# SMD_cree_driver_led-mosfet001.net
KiCad netlist of a schematic drawn in EAGLE
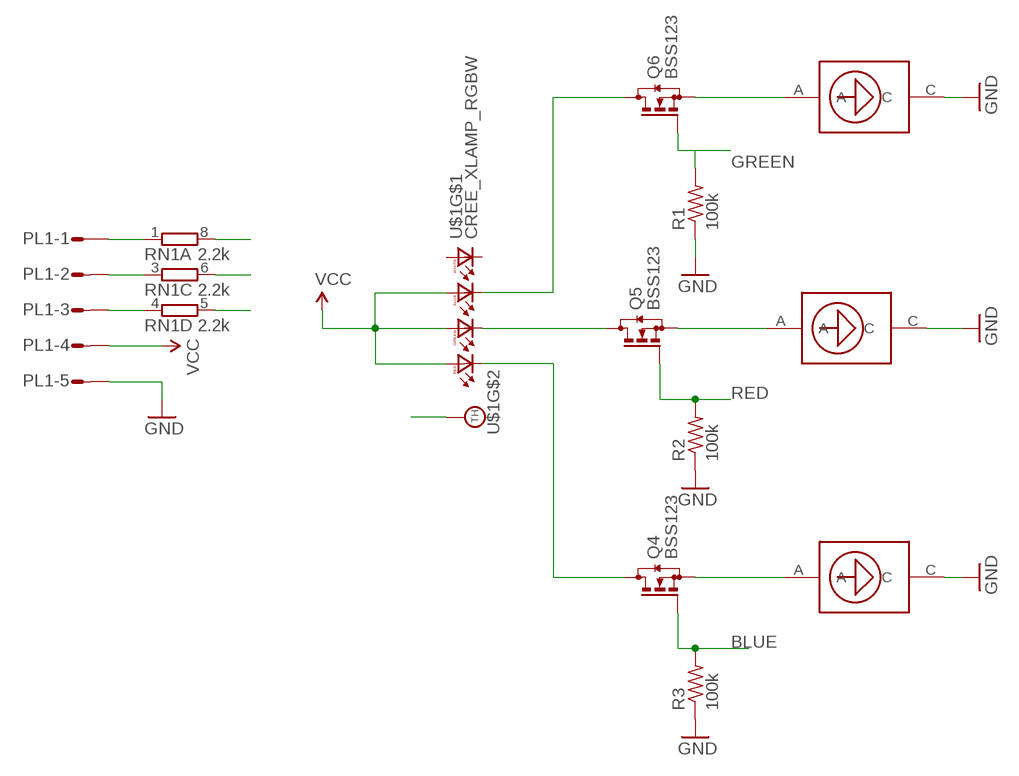
[diagram p0: schematic, sheet 1]

(export (version "E")
  (design (tool "Eeschema 10.0.6"))
  (components
    (comp (ref "PL1")
      (value "DF3-05R")
      (footprint "eagle-import:DF3R-05")
      (libsource (lib "eagle-import") (part "DF3-05R"))
    )
    (comp (ref "Q4")
      (value "BSS123")
      (footprint "eagle-import:SOT23")
      (libsource (lib "eagle-import") (part "BSS123"))
    )
    (comp (ref "Q5")
      (value "BSS123")
      (footprint "eagle-import:SOT23")
      (libsource (lib "eagle-import") (part "BSS123"))
    )
    (comp (ref "Q6")
      (value "BSS123")
      (footprint "eagle-import:SOT23")
      (libsource (lib "eagle-import") (part "BSS123"))
    )
    (comp (ref "R1")
      (value "100k")
      (footprint "eagle-import:R0402")
      (libsource (lib "eagle-import") (part "R-US_R0402"))
    )
    (comp (ref "R2")
      (value "100k")
      (footprint "eagle-import:R0402")
      (libsource (lib "eagle-import") (part "R-US_R0402"))
    )
    (comp (ref "R3")
      (value "100k")
      (footprint "eagle-import:R0402")
      (libsource (lib "eagle-import") (part "R-US_R0402"))
    )
    (comp (ref "RN1")
      (value "2.2k")
      (footprint "eagle-import:0603-ARC")
      (libsource (lib "eagle-import") (part "4R-N0603-ARC"))
    )
    (comp (ref "U$1")
      (value "CREE_XLAMP_RGBW")
      (footprint "eagle-import:CREE_XLAMP_XML")
      (libsource (lib "eagle-import") (part "CREE_XLAMP_RGBW"))
    )
    (comp (ref "U$2")
      (value "NSI50350AST3G")
      (footprint "eagle-import:SMC-2")
      (libsource (lib "eagle-import") (part "NSI50350AST3G"))
    )
    (comp (ref "U$3")
      (value "NSI50350AST3G")
      (footprint "eagle-import:SMC-2")
      (libsource (lib "eagle-import") (part "NSI50350AST3G"))
    )
    (comp (ref "U$4")
      (value "NSI50350AST3G")
      (footprint "eagle-import:SMC-2")
      (libsource (lib "eagle-import") (part "NSI50350AST3G"))
    )
  )
  (nets
    (net (code "1") (name "/BLUE") (class "Default")
      (node (ref "Q4") (pin "1") (pinfunction "G_1") (pintype "passive"))
      (node (ref "R3") (pin "2") (pinfunction "2_2") (pintype "passive"))
      (node (ref "RN1") (pin "5") (pinfunction "2_5") (pintype "passive"))
    )
    (net (code "2") (name "/GREEN") (class "Default")
      (node (ref "Q6") (pin "1") (pinfunction "G_1") (pintype "passive"))
      (node (ref "R1") (pin "2") (pinfunction "2_2") (pintype "passive"))
      (node (ref "RN1") (pin "8") (pinfunction "2_8") (pintype "passive"))
    )
    (net (code "3") (name "/RED") (class "Default")
      (node (ref "Q5") (pin "1") (pinfunction "G_1") (pintype "passive"))
      (node (ref "R2") (pin "2") (pinfunction "2_2") (pintype "passive"))
      (node (ref "RN1") (pin "6") (pinfunction "2_6") (pintype "passive"))
    )
    (net (code "4") (name "GND") (class "Default")
      (node (ref "PL1") (pin "5") (pinfunction "S_5") (pintype "passive"))
      (node (ref "R1") (pin "1") (pinfunction "1_1") (pintype "passive"))
      (node (ref "R2") (pin "1") (pinfunction "1_1") (pintype "passive"))
      (node (ref "R3") (pin "1") (pinfunction "1_1") (pintype "passive"))
      (node (ref "U$2") (pin "C") (pinfunction "C_C") (pintype "bidirectional"))
      (node (ref "U$3") (pin "C") (pinfunction "C_C") (pintype "bidirectional"))
      (node (ref "U$4") (pin "C") (pinfunction "C_C") (pintype "bidirectional"))
    )
    (net (code "5") (name "Net-(PL1A-S)") (class "Default")
      (node (ref "PL1") (pin "1") (pinfunction "S_1") (pintype "passive"))
      (node (ref "RN1") (pin "1") (pinfunction "1_1") (pintype "passive"))
    )
    (net (code "6") (name "Net-(PL1B-S)") (class "Default")
      (node (ref "PL1") (pin "2") (pinfunction "S_2") (pintype "passive"))
      (node (ref "RN1") (pin "3") (pinfunction "1_3") (pintype "passive"))
    )
    (net (code "7") (name "Net-(PL1C-S)") (class "Default")
      (node (ref "PL1") (pin "3") (pinfunction "S_3") (pintype "passive"))
      (node (ref "RN1") (pin "4") (pinfunction "1_4") (pintype "passive"))
    )
    (net (code "8") (name "Net-(Q4-D)") (class "Default")
      (node (ref "Q4") (pin "3") (pinfunction "D_3") (pintype "passive"))
      (node (ref "U$1") (pin "8") (pinfunction "RC_8") (pintype "passive"))
    )
    (net (code "9") (name "Net-(Q4-S)") (class "Default")
      (node (ref "Q4") (pin "2") (pinfunction "S_2") (pintype "passive"))
      (node (ref "U$4") (pin "A") (pinfunction "A_A") (pintype "bidirectional"))
    )
    (net (code "10") (name "Net-(Q5-D)") (class "Default")
      (node (ref "Q5") (pin "3") (pinfunction "D_3") (pintype "passive"))
      (node (ref "U$1") (pin "7") (pinfunction "GC_7") (pintype "passive"))
    )
    (net (code "11") (name "Net-(Q5-S)") (class "Default")
      (node (ref "Q5") (pin "2") (pinfunction "S_2") (pintype "passive"))
      (node (ref "U$3") (pin "A") (pinfunction "A_A") (pintype "bidirectional"))
    )
    (net (code "12") (name "Net-(Q6-D)") (class "Default")
      (node (ref "Q6") (pin "3") (pinfunction "D_3") (pintype "passive"))
      (node (ref "U$1") (pin "6") (pinfunction "BC_6") (pintype "passive"))
    )
    (net (code "13") (name "Net-(Q6-S)") (class "Default")
      (node (ref "Q6") (pin "2") (pinfunction "S_2") (pintype "passive"))
      (node (ref "U$2") (pin "A") (pinfunction "A_A") (pintype "bidirectional"))
    )
    (net (code "14") (name "VCC") (class "Default")
      (node (ref "PL1") (pin "4") (pinfunction "S_4") (pintype "passive"))
      (node (ref "U$1") (pin "1") (pinfunction "RA_1") (pintype "passive"))
      (node (ref "U$1") (pin "2") (pinfunction "GA_2") (pintype "passive"))
      (node (ref "U$1") (pin "3") (pinfunction "BA_3") (pintype "passive"))
    )
    (net (code "15") (name "unconnected-(U$1A-WA-Pad4)") (class "Default")
      (node (ref "U$1") (pin "4") (pinfunction "WA_4") (pintype "passive"))
    )
    (net (code "16") (name "unconnected-(U$1A-WC-Pad5)") (class "Default")
      (node (ref "U$1") (pin "5") (pinfunction "WC_5") (pintype "passive"))
    )
    (net (code "17") (name "unconnected-(U$1B-TH-PadP$1)") (class "Default")
      (node (ref "U$1") (pin "P$1") (pinfunction "TH_P$1") (pintype "passive"))
    )
  )
)
